# LEDPulserBoard_Split_3.net
KiCad netlist of a schematic drawn in EAGLE
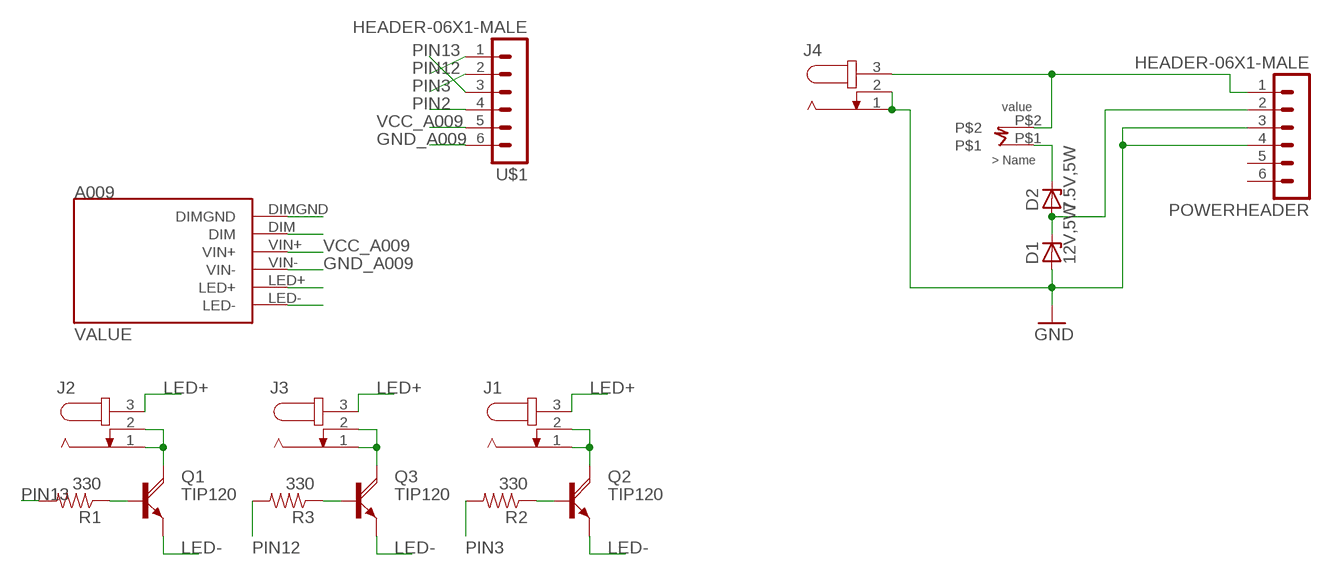
[diagram p0: schematic, sheet 1]

(export (version "E")
  (design (tool "Eeschema 10.0.6"))
  (components
    (comp (ref "D1")
      (value "12V,5W")
      (footprint "eagle-import:C1702-15")
      (libsource (lib "eagle-import") (part "1N5333"))
    )
    (comp (ref "D2")
      (value "7.5V,5W")
      (footprint "eagle-import:C1702-15")
      (libsource (lib "eagle-import") (part "1N5333"))
    )
    (comp (ref "J1")
      (value "JACK-PLUG0")
      (footprint "eagle-import:SPC4077")
      (libsource (lib "eagle-import") (part "JACK-PLUG0"))
    )
    (comp (ref "J2")
      (value "JACK-PLUG0")
      (footprint "eagle-import:SPC4077")
      (libsource (lib "eagle-import") (part "JACK-PLUG0"))
    )
    (comp (ref "J3")
      (value "JACK-PLUG0")
      (footprint "eagle-import:SPC4077")
      (libsource (lib "eagle-import") (part "JACK-PLUG0"))
    )
    (comp (ref "J4")
      (value "JACK-PLUG0")
      (footprint "eagle-import:SPC4077")
      (libsource (lib "eagle-import") (part "JACK-PLUG0"))
    )
    (comp (ref "POWERHEADER")
      (value "HEADER-06X1-MALE")
      (footprint "eagle-import:06X1-PTH")
      (libsource (lib "eagle-import") (part "HEADER-06X1?-MALE"))
    )
    (comp (ref "Q1")
      (value "TIP120")
      (footprint "eagle-import:TO220AH")
      (libsource (lib "eagle-import") (part "TIP120"))
    )
    (comp (ref "Q2")
      (value "TIP120")
      (footprint "eagle-import:TO220AH")
      (libsource (lib "eagle-import") (part "TIP120"))
    )
    (comp (ref "Q3")
      (value "TIP120")
      (footprint "eagle-import:TO220AH")
      (libsource (lib "eagle-import") (part "TIP120"))
    )
    (comp (ref "R1")
      (value "330")
      (footprint "eagle-import:AXIAL-0.4")
      (libsource (lib "eagle-import") (part "RESISTORPTH-1/4W"))
    )
    (comp (ref "R2")
      (value "330")
      (footprint "eagle-import:AXIAL-0.4")
      (libsource (lib "eagle-import") (part "RESISTORPTH-1/4W"))
    )
    (comp (ref "R3")
      (value "330")
      (footprint "eagle-import:AXIAL-0.4")
      (libsource (lib "eagle-import") (part "RESISTORPTH-1/4W"))
    )
    (comp (ref "U$1")
      (value "HEADER-06X1-MALE")
      (footprint "eagle-import:06X1-PTH")
      (libsource (lib "eagle-import") (part "HEADER-06X1?-MALE"))
    )
    (comp (ref "U$2")
      (value "BUCKBLOCKA009")
      (footprint "eagle-import:BUCKBLOCK")
      (libsource (lib "eagle-import") (part "BUCKBLOCKA009"))
    )
    (comp (ref "U$3")
      (value "5WRES")
      (footprint "eagle-import:5WAXIAL")
      (libsource (lib "eagle-import") (part "5WRES"))
    )
  )
  (nets
    (net (code "1") (name "/GND_A009") (class "Default")
      (node (ref "U$1") (pin "6") (pinfunction "6_6") (pintype "passive"))
      (node (ref "U$2") (pin "VIN-") (pinfunction "VIN-_VIN-") (pintype "bidirectional"))
    )
    (net (code "2") (name "/LED+") (class "Default")
      (node (ref "J1") (pin "3") (pinfunction "3_3") (pintype "passive"))
      (node (ref "J2") (pin "3") (pinfunction "3_3") (pintype "passive"))
      (node (ref "J3") (pin "3") (pinfunction "3_3") (pintype "passive"))
      (node (ref "U$2") (pin "LED+") (pinfunction "LED+_LED+") (pintype "bidirectional"))
    )
    (net (code "3") (name "/LED-") (class "Default")
      (node (ref "Q1") (pin "E") (pinfunction "E_E") (pintype "passive"))
      (node (ref "Q2") (pin "E") (pinfunction "E_E") (pintype "passive"))
      (node (ref "Q3") (pin "E") (pinfunction "E_E") (pintype "passive"))
      (node (ref "U$2") (pin "LED-") (pinfunction "LED-_LED-") (pintype "bidirectional"))
    )
    (net (code "4") (name "/PIN2") (class "Default")
      (node (ref "U$1") (pin "4") (pinfunction "4_4") (pintype "passive"))
    )
    (net (code "5") (name "/PIN3") (class "Default")
      (node (ref "R2") (pin "P$2") (pinfunction "2_P$2") (pintype "passive"))
      (node (ref "U$1") (pin "2") (pinfunction "2_2") (pintype "passive"))
    )
    (net (code "6") (name "/PIN12") (class "Default")
      (node (ref "R3") (pin "P$2") (pinfunction "2_P$2") (pintype "passive"))
      (node (ref "U$1") (pin "1") (pinfunction "1_1") (pintype "passive"))
    )
    (net (code "7") (name "/PIN13") (class "Default")
      (node (ref "R1") (pin "P$2") (pinfunction "2_P$2") (pintype "passive"))
      (node (ref "U$1") (pin "3") (pinfunction "3_3") (pintype "passive"))
    )
    (net (code "8") (name "/VCC_A009") (class "Default")
      (node (ref "U$1") (pin "5") (pinfunction "5_5") (pintype "passive"))
      (node (ref "U$2") (pin "VIN+") (pinfunction "VIN+_VIN+") (pintype "bidirectional"))
    )
    (net (code "9") (name "GND") (class "Default")
      (node (ref "D1") (pin "A") (pinfunction "A_A") (pintype "passive"))
      (node (ref "J4") (pin "1") (pinfunction "1_1") (pintype "passive"))
      (node (ref "J4") (pin "2") (pinfunction "2_2") (pintype "passive"))
      (node (ref "POWERHEADER") (pin "3") (pinfunction "3_3") (pintype "passive"))
      (node (ref "POWERHEADER") (pin "4") (pinfunction "4_4") (pintype "passive"))
    )
    (net (code "10") (name "Net-(D1-PadC)") (class "Default")
      (node (ref "D1") (pin "C") (pinfunction "C_C") (pintype "passive"))
      (node (ref "D2") (pin "A") (pinfunction "A_A") (pintype "passive"))
      (node (ref "POWERHEADER") (pin "2") (pinfunction "2_2") (pintype "passive"))
    )
    (net (code "11") (name "Net-(D2-PadC)") (class "Default")
      (node (ref "D2") (pin "C") (pinfunction "C_C") (pintype "passive"))
      (node (ref "U$3") (pin "P$1") (pinfunction "P$1_P$1") (pintype "bidirectional"))
    )
    (net (code "12") (name "Net-(J1-Pad1)") (class "Default")
      (node (ref "J1") (pin "1") (pinfunction "1_1") (pintype "passive"))
      (node (ref "J1") (pin "2") (pinfunction "2_2") (pintype "passive"))
      (node (ref "Q2") (pin "C") (pinfunction "C_C") (pintype "passive"))
    )
    (net (code "13") (name "Net-(J2-Pad1)") (class "Default")
      (node (ref "J2") (pin "1") (pinfunction "1_1") (pintype "passive"))
      (node (ref "J2") (pin "2") (pinfunction "2_2") (pintype "passive"))
      (node (ref "Q1") (pin "C") (pinfunction "C_C") (pintype "passive"))
    )
    (net (code "14") (name "Net-(J3-Pad1)") (class "Default")
      (node (ref "J3") (pin "1") (pinfunction "1_1") (pintype "passive"))
      (node (ref "J3") (pin "2") (pinfunction "2_2") (pintype "passive"))
      (node (ref "Q3") (pin "C") (pinfunction "C_C") (pintype "passive"))
    )
    (net (code "15") (name "Net-(J4-Pad3)") (class "Default")
      (node (ref "J4") (pin "3") (pinfunction "3_3") (pintype "passive"))
      (node (ref "POWERHEADER") (pin "1") (pinfunction "1_1") (pintype "passive"))
      (node (ref "U$3") (pin "P$2") (pinfunction "P$2_P$2") (pintype "bidirectional"))
    )
    (net (code "16") (name "Net-(R1-1)") (class "Default")
      (node (ref "Q1") (pin "B") (pinfunction "B_B") (pintype "passive"))
      (node (ref "R1") (pin "P$1") (pinfunction "1_P$1") (pintype "passive"))
    )
    (net (code "17") (name "Net-(R2-1)") (class "Default")
      (node (ref "Q2") (pin "B") (pinfunction "B_B") (pintype "passive"))
      (node (ref "R2") (pin "P$1") (pinfunction "1_P$1") (pintype "passive"))
    )
    (net (code "18") (name "Net-(R3-1)") (class "Default")
      (node (ref "Q3") (pin "B") (pinfunction "B_B") (pintype "passive"))
      (node (ref "R3") (pin "P$1") (pinfunction "1_P$1") (pintype "passive"))
    )
    (net (code "19") (name "unconnected-(POWERHEADER-Pad5)") (class "Default")
      (node (ref "POWERHEADER") (pin "5") (pinfunction "5_5") (pintype "passive"))
    )
    (net (code "20") (name "unconnected-(POWERHEADER-Pad6)") (class "Default")
      (node (ref "POWERHEADER") (pin "6") (pinfunction "6_6") (pintype "passive"))
    )
    (net (code "21") (name "unconnected-(U$2-PadDIM)") (class "Default")
      (node (ref "U$2") (pin "DIM") (pinfunction "DIM_DIM") (pintype "bidirectional"))
    )
    (net (code "22") (name "unconnected-(U$2-PadDIMGND)") (class "Default")
      (node (ref "U$2") (pin "DIMGND") (pinfunction "DIMGND_DIMGND") (pintype "bidirectional"))
    )
  )
)
